# Schematics_Sheet.net
KiCad netlist of a schematic drawn in Altium Designer
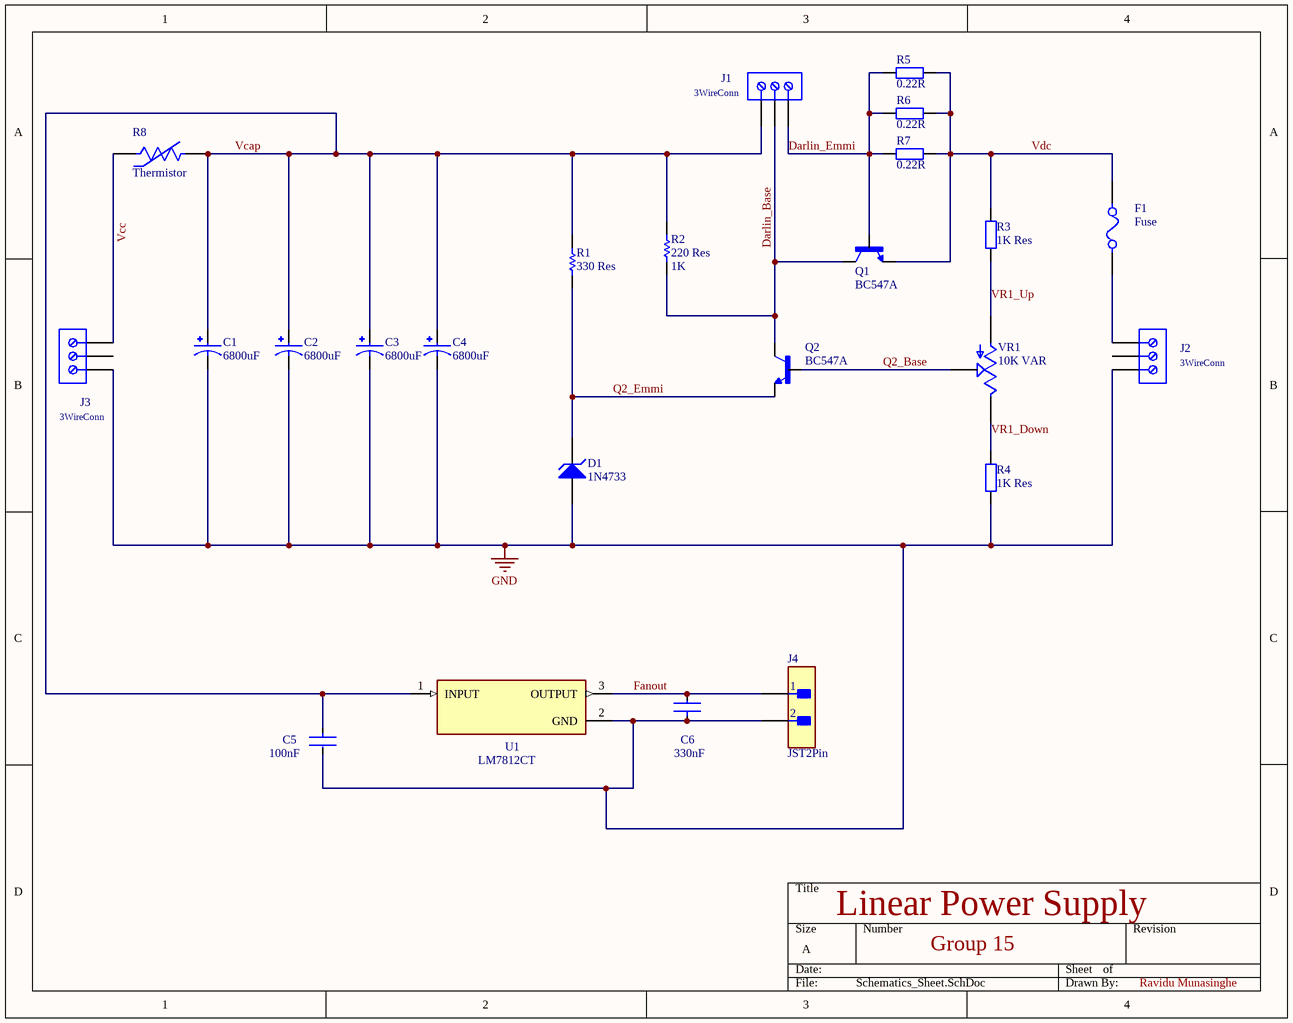
[diagram p0: Schematics_Sheet.SchDoc]

(export (version "E")
  (design (tool "Eeschema 10.0.6"))
  (components
    (comp (ref "C1")
      (value "6800uF")
      (footprint "Capacitor")
      (description "6800 µF 35 V Aluminum Electrolytic Capacitors Radial, Can - 2000 Hrs @ 85°C")
      (fields (field (name "MP") "EEUHD1V681B") (field (name "MF") "Panasonic"))
      (libsource (lib "Schematics") (part "493-11046-ND"))
    )
    (comp (ref "C2")
      (value "6800uF")
      (footprint "Capacitor")
      (description "6800 µF 35 V Aluminum Electrolytic Capacitors Radial, Can - 2000 Hrs @ 85°C")
      (fields (field (name "MP") "EEUHD1V681B") (field (name "MF") "Panasonic"))
      (libsource (lib "Schematics") (part "493-11046-ND"))
    )
    (comp (ref "C3")
      (value "6800uF")
      (footprint "Capacitor")
      (description "6800 µF 35 V Aluminum Electrolytic Capacitors Radial, Can - 2000 Hrs @ 85°C")
      (fields (field (name "MP") "EEUHD1V681B") (field (name "MF") "Panasonic"))
      (libsource (lib "Schematics") (part "493-11046-ND"))
    )
    (comp (ref "C4")
      (value "6800uF")
      (footprint "Capacitor")
      (description "6800 µF 35 V Aluminum Electrolytic Capacitors Radial, Can - 2000 Hrs @ 85°C")
      (fields (field (name "MP") "EEUHD1V681B") (field (name "MF") "Panasonic"))
      (libsource (lib "Schematics") (part "493-11046-ND"))
    )
    (comp (ref "C5")
      (value "100nF")
      (footprint "capacitor 0.1uf")
      (description "Cap Ceramic 100nF 100V X7R ±10% Radial 2.5mm +125°C Automotive Ammo Pack")
      (fields (field (name "TOLERANCE") "10%"))
      (libsource (lib "Schematics") (part "CMP-06035-052488-1"))
    )
    (comp (ref "C6")
      (value "330nF")
      (footprint "Cpacitor 0.33uf")
      (description "Cap Ceramic Monolithic 330nF 100V 10% Thru-Hole Bulk")
      (fields (field (name "TOLERANCE") "10%"))
      (libsource (lib "Schematics") (part "CMP-06035-045092-1"))
    )
    (comp (ref "D1")
      (value "1N4733")
      (footprint "1N4733")
      (description "Zener Diode 5.1V")
      (fields (field (name "PUBLISHER") "Altium Limited"))
      (libsource (lib "Schematics") (part "D Zener"))
    )
    (comp (ref "F1")
      (value "Fuse")
      (footprint "Fuse")
      (description "FUSE BLOK CARTRIDGE 600V 12A PCB")
      (fields
        (field (name "OCTOPART") "https://octopart.com/0031.8231-schurter-8659")
        (field (name "MANUFACTURER") "Schurter")
      )
      (libsource (lib "Schematics") (part "CMP-26292-000005-1"))
    )
    (comp (ref "J1")
      (value "3WireConn")
      (footprint "Connector")
      (description "Serie 2365 - 5.08 mm Horizontal Cable Entry Modular with Rising Cage Clamp WR-TBL, 3 pin")
      (fields
        (field (name "MANUFACTURER") "Wurth Elektronik")
        (field (name "PART NUMBER") "691236510003")
        (field (name "PUBLISHER") "WurthElektronik")
      )
      (libsource (lib "Schematics") (part "CMP-1502-02614-1"))
    )
    (comp (ref "J2")
      (value "3WireConn")
      (footprint "Connector")
      (description "Serie 2365 - 5.08 mm Horizontal Cable Entry Modular with Rising Cage Clamp WR-TBL, 3 pin")
      (fields
        (field (name "MANUFACTURER") "Wurth Elektronik")
        (field (name "PART NUMBER") "691236510003")
        (field (name "PUBLISHER") "WurthElektronik")
      )
      (libsource (lib "Schematics") (part "CMP-1502-02614-1"))
    )
    (comp (ref "J3")
      (value "3WireConn")
      (footprint "Connector")
      (description "Serie 2365 - 5.08 mm Horizontal Cable Entry Modular with Rising Cage Clamp WR-TBL, 3 pin")
      (fields
        (field (name "MANUFACTURER") "Wurth Elektronik")
        (field (name "PART NUMBER") "691236510003")
        (field (name "PUBLISHER") "WurthElektronik")
      )
      (libsource (lib "Schematics") (part "CMP-1502-02614-1"))
    )
    (comp (ref "J4")
      (value "JST2Pin")
      (footprint "JST 2 Pin")
      (description "CONN HEADER VERT 2POS 3.96MM")
      (libsource (lib "Schematics") (part "CMP-17439-000031-1"))
    )
    (comp (ref "Q1")
      (value "BC547A")
      (footprint "BC547")
      (description "Bipolar (BJT) Transistor NPN 45 V 100 mA 300MHz 625 mW Through Hole TO-92")
      (fields (field (name "MF") "ON Semiconductor"))
      (libsource (lib "Schematics") (part "2368-BC547A-ND"))
    )
    (comp (ref "Q2")
      (value "BC547A")
      (footprint "BC547")
      (description "Bipolar (BJT) Transistor NPN 45 V 100 mA 300MHz 625 mW Through Hole TO-92")
      (fields (field (name "MF") "ON Semiconductor"))
      (libsource (lib "") (part "2368-BC547A-ND_1"))
    )
    (comp (ref "R1")
      (value "330 Res")
      (footprint "330/470ohm")
      (description "330 Ohms ±5% 1W Through Hole Resistor Axial Fusible, Safety")
      (fields (field (name "PUBLISHER") "Altium Limited"))
      (libsource (lib "Schematics") (part "2368-F1W133-ND"))
    )
    (comp (ref "R2")
      (value "220 Res")
      (footprint "330/470ohm")
      (description "220 Ohms ±5% 1W Through Hole Resistor Axial Flame Proof, Safety Metal Oxide Film")
      (fields (field (name "ALTIUM_VALUE") "1K") (field (name "PUBLISHER") "Altium Limited"))
      (libsource (lib "Schematics") (part "470W-1-ND"))
    )
    (comp (ref "R3")
      (value "1K Res")
      (footprint "AXIAL-0.4")
      (description "1 kOhms ±5% 0.25W, 1/4W Through Hole Resistor Axial Flame Retardant Coating, Safety Carbon Film")
      (fields (field (name "PUBLISHER") "Altium Limited"))
      (libsource (lib "Schematics") (part "CF14JT1K00TR-ND"))
    )
    (comp (ref "R4")
      (value "1K Res")
      (footprint "AXIAL-0.4")
      (description "1 kOhms ±5% 0.25W, 1/4W Through Hole Resistor Axial Flame Retardant Coating, Safety Carbon Film")
      (fields (field (name "PUBLISHER") "Altium Limited"))
      (libsource (lib "Schematics") (part "CF14JT1K00TR-ND"))
    )
    (comp (ref "R5")
      (value "0.22R")
      (footprint "0.22 Ohm Ceramic Res")
      (description "Wirewound Resistors - Through Hole 0.22ohms 5% Tol 7W")
      (fields (field (name "PUBLISHER") "Altium Limited"))
      (libsource (lib "Schematics") (part "280-CR10-0.22-RC"))
    )
    (comp (ref "R6")
      (value "0.22R")
      (footprint "0.22 Ohm Ceramic Res")
      (description "Wirewound Resistors - Through Hole 0.22ohms 5% Tol 7W")
      (fields (field (name "PUBLISHER") "Altium Limited"))
      (libsource (lib "Schematics") (part "280-CR10-0.22-RC"))
    )
    (comp (ref "R7")
      (value "0.22R")
      (footprint "0.22 Ohm Ceramic Res")
      (description "Wirewound Resistors - Through Hole 0.22ohms 5% Tol 7W")
      (fields (field (name "PUBLISHER") "Altium Limited"))
      (libsource (lib "Schematics") (part "280-CR10-0.22-RC"))
    )
    (comp (ref "R8")
      (value "Thermistor")
      (footprint "Thermistor")
      (description "Thermistor PTC 470Ω 2-Pin Screw Mount Radial Bulk")
      (fields (field (name "TOLERANCE") "20%") (field (name "VOLTAGE") "16V"))
      (libsource (lib "Schematics") (part "CMP-06022-000249-1"))
    )
    (comp (ref "U1")
      (value "LM7812CT")
      (footprint "Fan_Regulator")
      (description "IC REG LINEAR 12V 1A TO220-3")
      (fields
        (field (name "OCTOPART") "https://octopart.com/lm7812ct-on+semiconductor-14383031")
        (field (name "OBSOLETE PART") "true")
      )
      (libsource (lib "Schematics") (part "CMP-07128-000015-1"))
    )
    (comp (ref "VR1")
      (value "10K VAR")
      (footprint "Var_Res_Final")
      (description "10 kOhms 0.1W, 1/10W PC Pins Through Hole Trimmer Potentiometer Carbon 1.0 Turn Top Adjustment")
      (fields (field (name "MF") "Bourns") (field (name "DIGI-KEY_PART_NUMBER") "118-3362P-1-503RLFCT-ND"))
      (libsource (lib "Schematics") (part "478-601030-ND"))
    )
  )
  (nets
    (net (code "1") (name "/Darlin_Base") (class "Default")
      (node (ref "J1") (pin "2") (pinfunction "2_2") (pintype "passive"))
      (node (ref "Q1") (pin "1") (pinfunction "C_1") (pintype "passive"))
      (node (ref "Q2") (pin "1") (pinfunction "C_1") (pintype "passive"))
      (node (ref "R2") (pin "2") (pinfunction "2_2") (pintype "passive"))
    )
    (net (code "2") (name "/Darlin_Emmi") (class "Default")
      (node (ref "J1") (pin "3") (pinfunction "3_3") (pintype "passive"))
      (node (ref "Q1") (pin "2") (pinfunction "B_2") (pintype "passive"))
      (node (ref "R5") (pin "1") (pinfunction "1_1") (pintype "passive"))
      (node (ref "R6") (pin "1") (pinfunction "1_1") (pintype "passive"))
      (node (ref "R7") (pin "1") (pinfunction "1_1") (pintype "passive"))
    )
    (net (code "3") (name "/Fanout") (class "Default")
      (node (ref "C6") (pin "2") (pinfunction "2_2") (pintype "passive"))
      (node (ref "J4") (pin "1") (pinfunction "1_1") (pintype "passive"))
      (node (ref "U1") (pin "3") (pinfunction "OUTPUT_3") (pintype "output"))
    )
    (net (code "4") (name "/Q2_Base") (class "Default")
      (node (ref "Q2") (pin "2") (pinfunction "B_2") (pintype "passive"))
      (node (ref "VR1") (pin "2") (pinfunction "WIPER_2") (pintype "passive"))
    )
    (net (code "5") (name "/Q2_Emmi") (class "Default")
      (node (ref "D1") (pin "2") (pinfunction "K_2") (pintype "passive"))
      (node (ref "Q2") (pin "3") (pinfunction "E_3") (pintype "passive"))
      (node (ref "R1") (pin "2") (pinfunction "2_2") (pintype "passive"))
    )
    (net (code "6") (name "/VR1_Down") (class "Default")
      (node (ref "R4") (pin "2") (pinfunction "2_2") (pintype "passive"))
      (node (ref "VR1") (pin "3") (pinfunction "CW_3") (pintype "passive"))
    )
    (net (code "7") (name "/VR1_Up") (class "Default")
      (node (ref "R3") (pin "1") (pinfunction "1_1") (pintype "passive"))
      (node (ref "VR1") (pin "1") (pinfunction "CCW_1") (pintype "passive"))
    )
    (net (code "8") (name "/Vcap") (class "Default")
      (node (ref "C1") (pin "1") (pinfunction "P_1") (pintype "passive"))
      (node (ref "C2") (pin "1") (pinfunction "P_1") (pintype "passive"))
      (node (ref "C3") (pin "1") (pinfunction "P_1") (pintype "passive"))
      (node (ref "C4") (pin "1") (pinfunction "P_1") (pintype "passive"))
      (node (ref "C5") (pin "1") (pinfunction "1_1") (pintype "passive"))
      (node (ref "J1") (pin "1") (pinfunction "1_1") (pintype "passive"))
      (node (ref "R1") (pin "1") (pinfunction "1_1") (pintype "passive"))
      (node (ref "R2") (pin "1") (pinfunction "1_1") (pintype "passive"))
      (node (ref "R8") (pin "2") (pinfunction "2_2") (pintype "passive"))
      (node (ref "U1") (pin "1") (pinfunction "INPUT_1") (pintype "input"))
    )
    (net (code "9") (name "/Vcc") (class "Default")
      (node (ref "J3") (pin "3") (pinfunction "3_3") (pintype "passive"))
      (node (ref "R8") (pin "1") (pinfunction "1_1") (pintype "passive"))
    )
    (net (code "10") (name "/Vdc") (class "Default")
      (node (ref "F1") (pin "2") (pinfunction "2_2") (pintype "passive"))
      (node (ref "Q1") (pin "3") (pinfunction "E_3") (pintype "passive"))
      (node (ref "R3") (pin "2") (pinfunction "2_2") (pintype "passive"))
      (node (ref "R5") (pin "2") (pinfunction "2_2") (pintype "passive"))
      (node (ref "R6") (pin "2") (pinfunction "2_2") (pintype "passive"))
      (node (ref "R7") (pin "2") (pinfunction "2_2") (pintype "passive"))
    )
    (net (code "11") (name "GND") (class "Default")
      (node (ref "C1") (pin "2") (pinfunction "N_2") (pintype "passive"))
      (node (ref "C2") (pin "2") (pinfunction "N_2") (pintype "passive"))
      (node (ref "C3") (pin "2") (pinfunction "N_2") (pintype "passive"))
      (node (ref "C4") (pin "2") (pinfunction "N_2") (pintype "passive"))
      (node (ref "C5") (pin "2") (pinfunction "2_2") (pintype "passive"))
      (node (ref "C6") (pin "1") (pinfunction "1_1") (pintype "passive"))
      (node (ref "D1") (pin "1") (pinfunction "A_1") (pintype "passive"))
      (node (ref "J2") (pin "3") (pinfunction "3_3") (pintype "passive"))
      (node (ref "J3") (pin "1") (pinfunction "1_1") (pintype "passive"))
      (node (ref "J4") (pin "2") (pinfunction "2_2") (pintype "passive"))
      (node (ref "R4") (pin "1") (pinfunction "1_1") (pintype "passive"))
      (node (ref "U1") (pin "2") (pinfunction "GND_2") (pintype "power_in"))
    )
    (net (code "12") (name "Net-(F1-Pad1)") (class "Default")
      (node (ref "F1") (pin "1") (pinfunction "1_1") (pintype "passive"))
      (node (ref "J2") (pin "1") (pinfunction "1_1") (pintype "passive"))
    )
    (net (code "13") (name "unconnected-(J2-Pad2)") (class "Default")
      (node (ref "J2") (pin "2") (pinfunction "2_2") (pintype "passive"))
    )
    (net (code "14") (name "unconnected-(J3-Pad2)") (class "Default")
      (node (ref "J3") (pin "2") (pinfunction "2_2") (pintype "passive"))
    )
  )
)
